# UART_Block.net
KiCad netlist of a schematic drawn in EAGLE
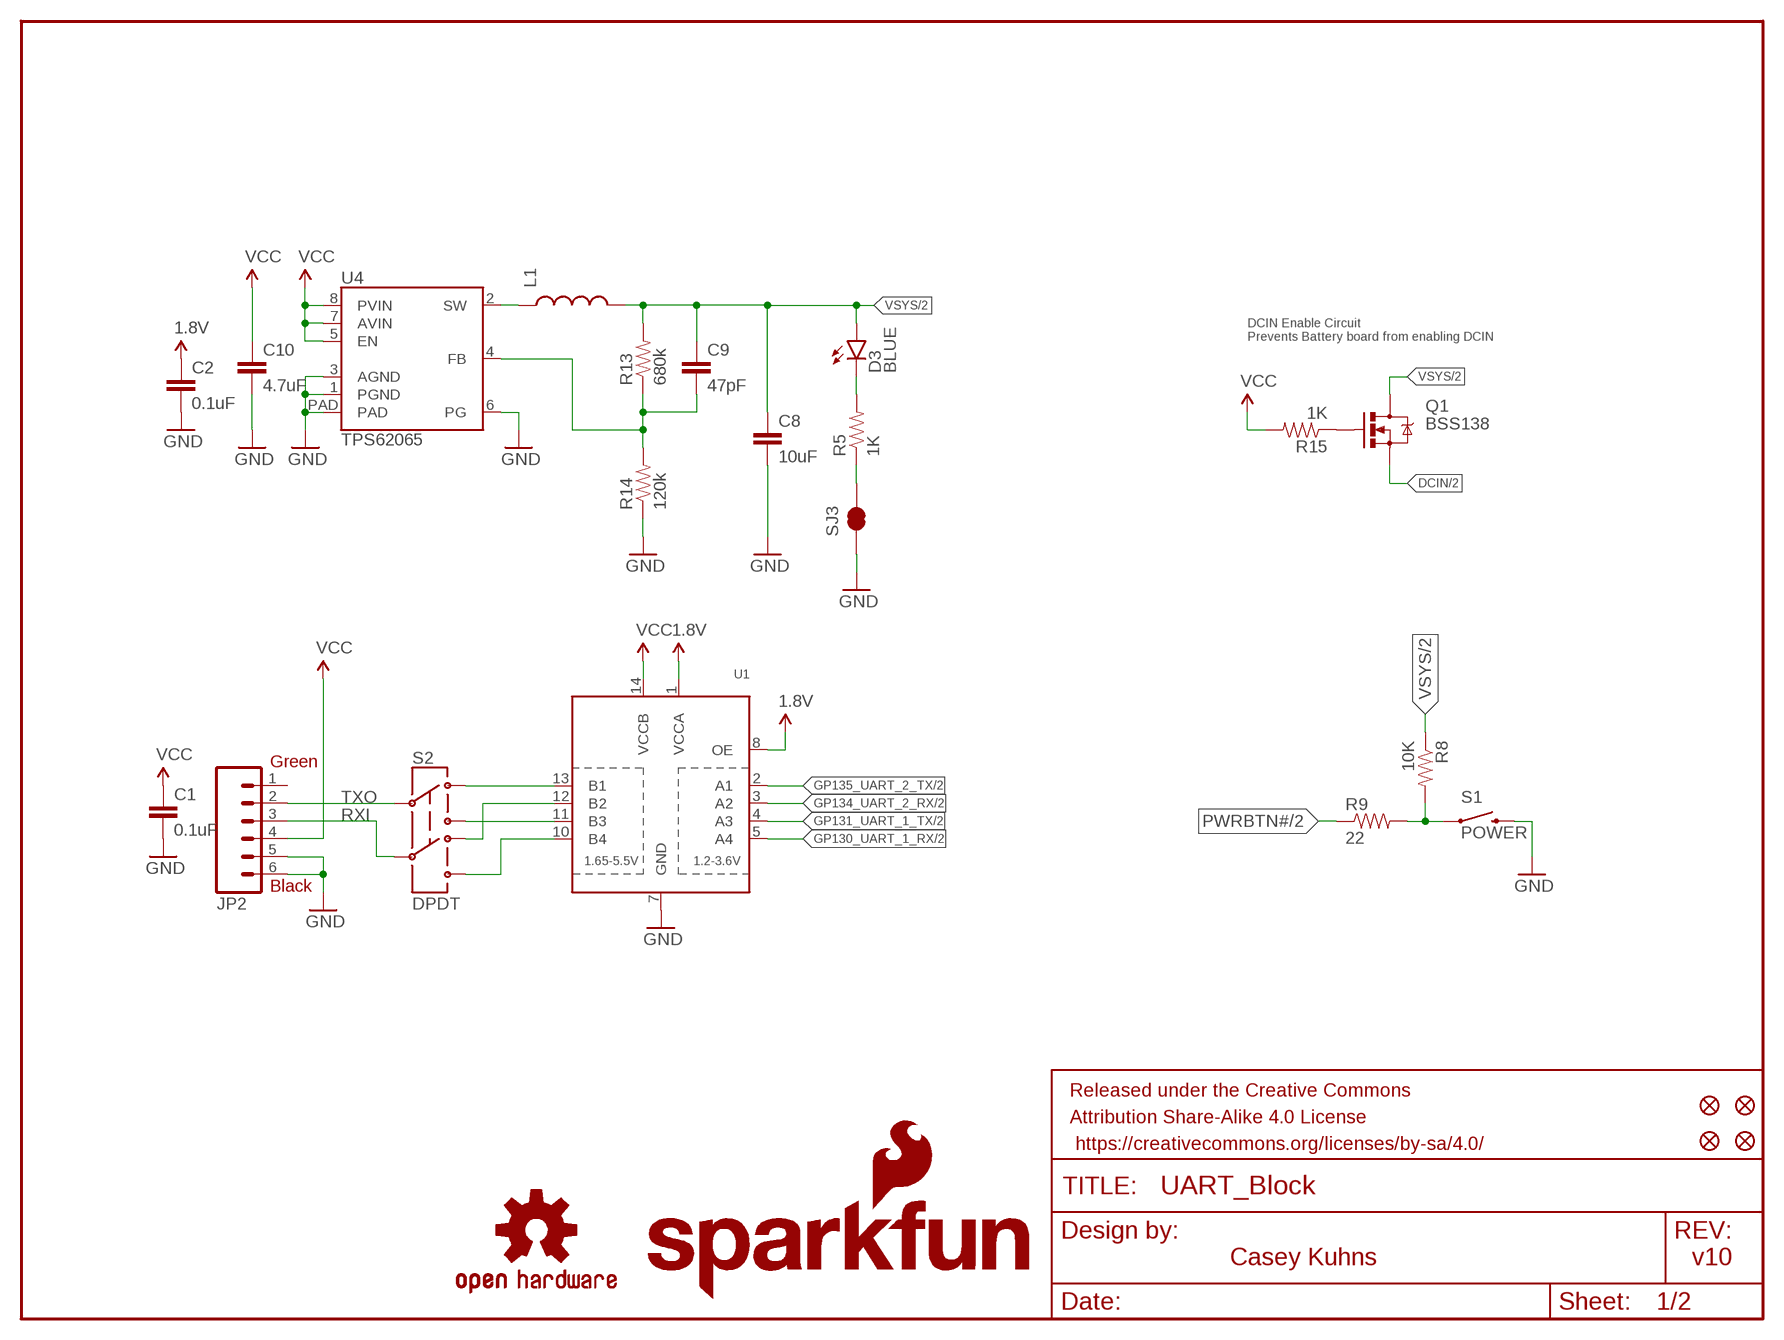
[diagram p0: schematic, sheet 1]
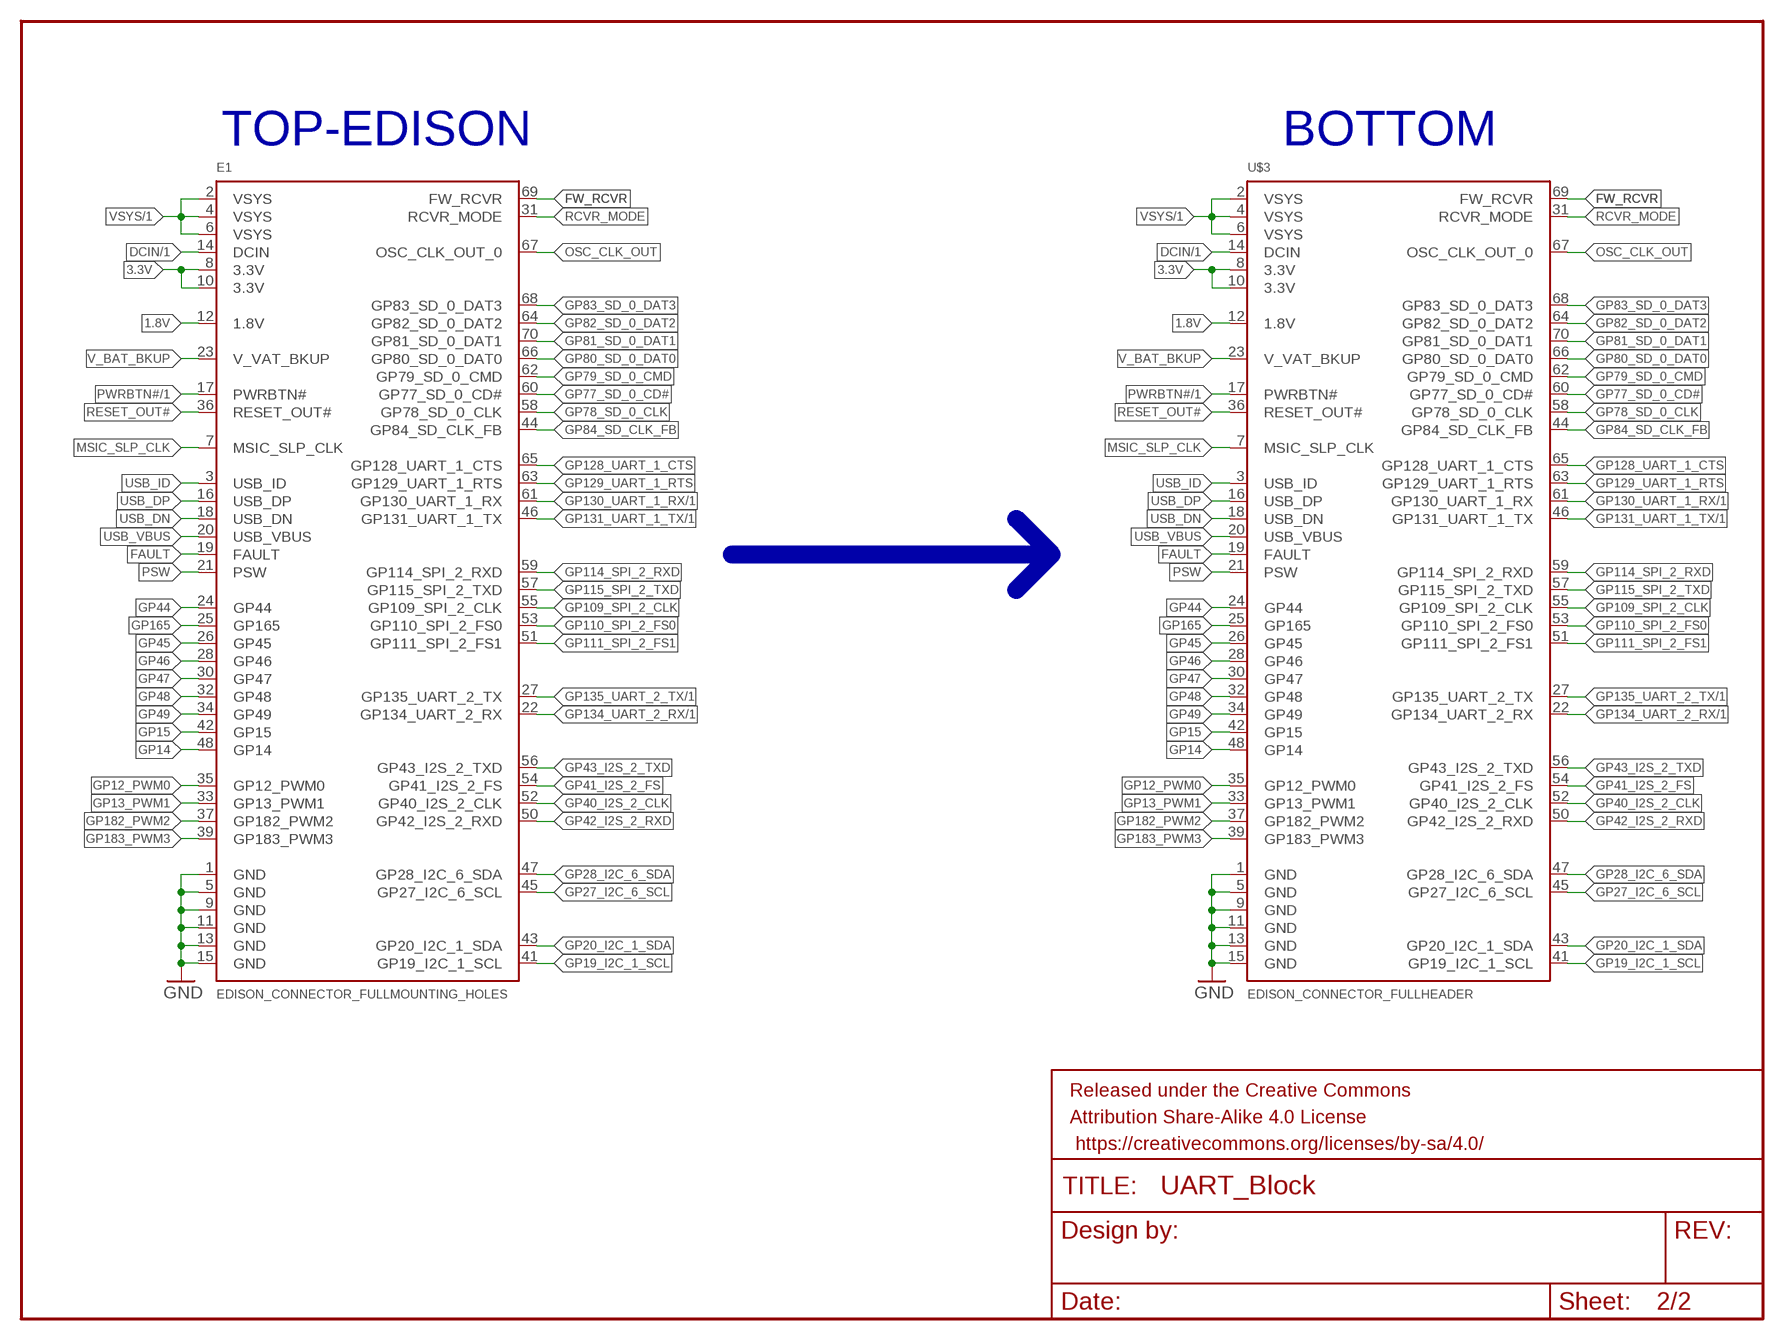
[diagram p1: schematic, sheet 2]

(export (version "E")
  (design (tool "Eeschema 10.0.6"))
  (components
    (comp (ref "E1")
      (value "EDISON_CONNECTOR_FULLMOUNTING_HOLES")
      (footprint "eagle-import:EDISON_DAUGHTER")
      (libsource (lib "eagle-import") (part "EDISON_CONNECTOR_FULLMOUNTING_HOLES"))
    )
    (comp (ref "FRAME2")
      (value "FRAME-LETTER")
      (footprint "eagle-import:CREATIVE_COMMONS")
      (libsource (lib "eagle-import") (part "FRAME-LETTER"))
    )
    (comp (ref "U$3")
      (value "EDISON_CONNECTOR_FULLHEADER")
      (footprint "eagle-import:DF40C-70DP-0.4(51)")
      (libsource (lib "eagle-import") (part "EDISON_CONNECTOR_FULLHEADER"))
    )
    (comp (ref "C1")
      (value "0.1uF")
      (footprint "eagle-import:0603-CAP")
      (libsource (lib "eagle-import") (part "0.1UF-25V(+80/-20%)(0603)"))
    )
    (comp (ref "C2")
      (value "0.1uF")
      (footprint "eagle-import:0603-CAP")
      (libsource (lib "eagle-import") (part "0.1UF-25V(+80/-20%)(0603)"))
    )
    (comp (ref "C8")
      (value "10uF")
      (footprint "eagle-import:1206")
      (libsource (lib "eagle-import") (part "10UF-6.3V-20%(1206)"))
    )
    (comp (ref "C9")
      (value "47pF")
      (footprint "eagle-import:0603-CAP")
      (libsource (lib "eagle-import") (part "47PF-50V-5%(0603)"))
    )
    (comp (ref "C10")
      (value "4.7uF")
      (footprint "eagle-import:0603-CAP")
      (libsource (lib "eagle-import") (part "4.7UF-6.3V-10%(0603)0603"))
    )
    (comp (ref "D3")
      (value "BLUE")
      (footprint "eagle-import:LED-0603")
      (libsource (lib "eagle-import") (part "LED-BLUE0603"))
    )
    (comp (ref "FID1")
      (value "FIDUCIAL1X2")
      (footprint "eagle-import:FIDUCIAL-1X2")
      (libsource (lib "eagle-import") (part "FIDUCIAL1X2"))
    )
    (comp (ref "FID2")
      (value "FIDUCIAL1X2")
      (footprint "eagle-import:FIDUCIAL-1X2")
      (libsource (lib "eagle-import") (part "FIDUCIAL1X2"))
    )
    (comp (ref "FID3")
      (value "FIDUCIAL1X2")
      (footprint "eagle-import:FIDUCIAL-1X2")
      (libsource (lib "eagle-import") (part "FIDUCIAL1X2"))
    )
    (comp (ref "FID4")
      (value "FIDUCIAL1X2")
      (footprint "eagle-import:FIDUCIAL-1X2")
      (libsource (lib "eagle-import") (part "FIDUCIAL1X2"))
    )
    (comp (ref "FRAME1")
      (value "FRAME-LETTER")
      (footprint "eagle-import:CREATIVE_COMMONS")
      (libsource (lib "eagle-import") (part "FRAME-LETTER"))
    )
    (comp (ref "JP2")
      (value "M06SMD")
      (footprint "eagle-import:1X06-SMD")
      (libsource (lib "eagle-import") (part "M06SMD"))
    )
    (comp (ref "L1")
      (value "INDUCTOR")
      (footprint "eagle-import:INDUCTOR-SRP4020")
      (libsource (lib "eagle-import") (part "INDUCTOR"))
    )
    (comp (ref "LOGO1")
      (value "SFE_LOGO_NAME_FLAME.1_INCH")
      (footprint "eagle-import:SFE_LOGO_NAME_FLAME_.1")
      (libsource (lib "eagle-import") (part "SFE_LOGO_NAME_FLAME.1_INCH"))
    )
    (comp (ref "LOGO4")
      (value "OSHW-LOGOS")
      (footprint "eagle-import:OSHW-LOGO-S")
      (libsource (lib "eagle-import") (part "OSHW-LOGOS"))
    )
    (comp (ref "Q1")
      (value "BSS138")
      (footprint "eagle-import:SOT23-3")
      (libsource (lib "eagle-import") (part "MOSFET-NCHANNELBSS138"))
    )
    (comp (ref "R5")
      (value "1K")
      (footprint "eagle-import:0603-RES")
      (libsource (lib "eagle-import") (part "1KOHM1/10W1%(0603)"))
    )
    (comp (ref "R8")
      (value "10K")
      (footprint "eagle-import:0603-RES")
      (libsource (lib "eagle-import") (part "10KOHM1/10W1%(0603)0603"))
    )
    (comp (ref "R9")
      (value "22")
      (footprint "eagle-import:0603-RES")
      (libsource (lib "eagle-import") (part "22OHM1/10W1%(0603)"))
    )
    (comp (ref "R13")
      (value "680k")
      (footprint "eagle-import:0603-RES")
      (libsource (lib "eagle-import") (part "RESISTOR0603"))
    )
    (comp (ref "R14")
      (value "120k")
      (footprint "eagle-import:0603-RES")
      (libsource (lib "eagle-import") (part "RESISTOR0603"))
    )
    (comp (ref "R15")
      (value "1K")
      (footprint "eagle-import:0603-RES")
      (libsource (lib "eagle-import") (part "1KOHM1/10W1%(0603)"))
    )
    (comp (ref "S1")
      (value "POWER")
      (footprint "eagle-import:TACTILE_SWITCH-SMD-RIGHT-ANGLE")
      (libsource (lib "eagle-import") (part "SWITCH-MOMENTARY-2TACTILE-SWITCH-SMD-RIGHT-ANGLE"))
    )
    (comp (ref "S2")
      (value "DPDT")
      (footprint "eagle-import:AYZ0202")
      (libsource (lib "eagle-import") (part "SWITCH-DPDTAYZ0202"))
    )
    (comp (ref "SJ3")
      (value "JUMPER-PAD-2-NC_BY_TRACE")
      (footprint "eagle-import:PAD-JUMPER-2-NC_BY_TRACE_YES_SILK")
      (libsource (lib "eagle-import") (part "JUMPER-PAD-2-NC_BY_TRACE"))
    )
    (comp (ref "U1")
      (value "TXB0104PWRSOIC14")
      (footprint "eagle-import:SO14")
      (libsource (lib "eagle-import") (part "TXB0104PWRSOIC14"))
    )
    (comp (ref "U4")
      (value "TPS62065")
      (footprint "eagle-import:WSON-8-PAD")
      (libsource (lib "eagle-import") (part "TPS62065"))
    )
  )
  (nets
    (net (code "1") (name "1.8V") (class "Default")
      (node (ref "C2") (pin "1") (pinfunction "1_1") (pintype "passive"))
      (node (ref "E1") (pin "12") (pinfunction "1.8V_12") (pintype "bidirectional"))
      (node (ref "U$3") (pin "12") (pinfunction "1.8V_12") (pintype "bidirectional"))
      (node (ref "U1") (pin "1") (pinfunction "VCCA_1") (pintype "bidirectional"))
      (node (ref "U1") (pin "8") (pinfunction "OE_8") (pintype "bidirectional"))
    )
    (net (code "2") (name "3.3V") (class "Default")
      (node (ref "E1") (pin "10") (pinfunction "3.3V_10") (pintype "bidirectional"))
      (node (ref "E1") (pin "8") (pinfunction "3.3V_8") (pintype "bidirectional"))
      (node (ref "U$3") (pin "10") (pinfunction "3.3V_10") (pintype "bidirectional"))
      (node (ref "U$3") (pin "8") (pinfunction "3.3V_8") (pintype "bidirectional"))
    )
    (net (code "3") (name "DCIN") (class "Default")
      (node (ref "E1") (pin "14") (pinfunction "DCIN_14") (pintype "bidirectional"))
      (node (ref "Q1") (pin "2") (pinfunction "S_2") (pintype "passive"))
      (node (ref "U$3") (pin "14") (pinfunction "DCIN_14") (pintype "bidirectional"))
    )
    (net (code "4") (name "FAULT") (class "Default")
      (node (ref "E1") (pin "19") (pinfunction "FAULT_19") (pintype "bidirectional"))
      (node (ref "U$3") (pin "19") (pinfunction "FAULT_19") (pintype "bidirectional"))
    )
    (net (code "5") (name "FW_RCVR") (class "Default")
      (node (ref "E1") (pin "69") (pinfunction "FW_RCVR_69") (pintype "bidirectional"))
      (node (ref "U$3") (pin "69") (pinfunction "FW_RCVR_69") (pintype "bidirectional"))
    )
    (net (code "6") (name "GND") (class "Default")
      (node (ref "C1") (pin "2") (pinfunction "2_2") (pintype "passive"))
      (node (ref "C10") (pin "2") (pinfunction "2_2") (pintype "passive"))
      (node (ref "C2") (pin "2") (pinfunction "2_2") (pintype "passive"))
      (node (ref "C8") (pin "2") (pinfunction "2_2") (pintype "passive"))
      (node (ref "E1") (pin "1") (pinfunction "GND_1") (pintype "bidirectional"))
      (node (ref "E1") (pin "11") (pinfunction "GND_11") (pintype "bidirectional"))
      (node (ref "E1") (pin "13") (pinfunction "GND_13") (pintype "bidirectional"))
      (node (ref "E1") (pin "15") (pinfunction "GND_15") (pintype "bidirectional"))
      (node (ref "E1") (pin "5") (pinfunction "GND_5") (pintype "bidirectional"))
      (node (ref "E1") (pin "9") (pinfunction "GND_9") (pintype "bidirectional"))
      (node (ref "JP2") (pin "5") (pinfunction "5_5") (pintype "passive"))
      (node (ref "JP2") (pin "6") (pinfunction "6_6") (pintype "passive"))
      (node (ref "R14") (pin "1") (pinfunction "1_1") (pintype "passive"))
      (node (ref "S1") (pin "2") (pinfunction "2_2") (pintype "passive"))
      (node (ref "SJ3") (pin "1") (pinfunction "1_1") (pintype "passive"))
      (node (ref "U$3") (pin "1") (pinfunction "GND_1") (pintype "bidirectional"))
      (node (ref "U$3") (pin "11") (pinfunction "GND_11") (pintype "bidirectional"))
      (node (ref "U$3") (pin "13") (pinfunction "GND_13") (pintype "bidirectional"))
      (node (ref "U$3") (pin "15") (pinfunction "GND_15") (pintype "bidirectional"))
      (node (ref "U$3") (pin "5") (pinfunction "GND_5") (pintype "bidirectional"))
      (node (ref "U$3") (pin "9") (pinfunction "GND_9") (pintype "bidirectional"))
      (node (ref "U1") (pin "7") (pinfunction "GND_7") (pintype "bidirectional"))
      (node (ref "U4") (pin "1") (pinfunction "PGND_1") (pintype "bidirectional"))
      (node (ref "U4") (pin "3") (pinfunction "AGND_3") (pintype "bidirectional"))
      (node (ref "U4") (pin "6") (pinfunction "PG_6") (pintype "bidirectional"))
      (node (ref "U4") (pin "PAD") (pinfunction "PAD_PAD") (pintype "bidirectional"))
    )
    (net (code "7") (name "GP12_PWM0") (class "Default")
      (node (ref "E1") (pin "35") (pinfunction "GP12_PWM0_35") (pintype "bidirectional"))
      (node (ref "U$3") (pin "35") (pinfunction "GP12_PWM0_35") (pintype "bidirectional"))
    )
    (net (code "8") (name "GP13_PWM1") (class "Default")
      (node (ref "E1") (pin "33") (pinfunction "GP13_PWM1_33") (pintype "bidirectional"))
      (node (ref "U$3") (pin "33") (pinfunction "GP13_PWM1_33") (pintype "bidirectional"))
    )
    (net (code "9") (name "GP14") (class "Default")
      (node (ref "E1") (pin "48") (pinfunction "GP14_48") (pintype "bidirectional"))
      (node (ref "U$3") (pin "48") (pinfunction "GP14_48") (pintype "bidirectional"))
    )
    (net (code "10") (name "GP15") (class "Default")
      (node (ref "E1") (pin "42") (pinfunction "GP15_42") (pintype "bidirectional"))
      (node (ref "U$3") (pin "42") (pinfunction "GP15_42") (pintype "bidirectional"))
    )
    (net (code "11") (name "GP19_I2C_1_SCL") (class "Default")
      (node (ref "E1") (pin "41") (pinfunction "GP19_I2C_1_SCL_41") (pintype "bidirectional"))
      (node (ref "U$3") (pin "41") (pinfunction "GP19_I2C_1_SCL_41") (pintype "bidirectional"))
    )
    (net (code "12") (name "GP20_I2C_1_SDA") (class "Default")
      (node (ref "E1") (pin "43") (pinfunction "GP20_I2C_1_SDA_43") (pintype "bidirectional"))
      (node (ref "U$3") (pin "43") (pinfunction "GP20_I2C_1_SDA_43") (pintype "bidirectional"))
    )
    (net (code "13") (name "GP27_I2C_6_SCL") (class "Default")
      (node (ref "E1") (pin "45") (pinfunction "GP27_I2C_6_SCL_45") (pintype "bidirectional"))
      (node (ref "U$3") (pin "45") (pinfunction "GP27_I2C_6_SCL_45") (pintype "bidirectional"))
    )
    (net (code "14") (name "GP28_I2C_6_SDA") (class "Default")
      (node (ref "E1") (pin "47") (pinfunction "GP28_I2C_6_SDA_47") (pintype "bidirectional"))
      (node (ref "U$3") (pin "47") (pinfunction "GP28_I2C_6_SDA_47") (pintype "bidirectional"))
    )
    (net (code "15") (name "GP40_I2S_2_CLK") (class "Default")
      (node (ref "E1") (pin "52") (pinfunction "GP40_I2S_2_CLK_52") (pintype "bidirectional"))
      (node (ref "U$3") (pin "52") (pinfunction "GP40_I2S_2_CLK_52") (pintype "bidirectional"))
    )
    (net (code "16") (name "GP41_I2S_2_FS") (class "Default")
      (node (ref "E1") (pin "54") (pinfunction "GP41_I2S_2_FS_54") (pintype "bidirectional"))
      (node (ref "U$3") (pin "54") (pinfunction "GP41_I2S_2_FS_54") (pintype "bidirectional"))
    )
    (net (code "17") (name "GP42_I2S_2_RXD") (class "Default")
      (node (ref "E1") (pin "50") (pinfunction "GP42_I2S_2_RXD_50") (pintype "bidirectional"))
      (node (ref "U$3") (pin "50") (pinfunction "GP42_I2S_2_RXD_50") (pintype "bidirectional"))
    )
    (net (code "18") (name "GP43_I2S_2_TXD") (class "Default")
      (node (ref "E1") (pin "56") (pinfunction "GP43_I2S_2_TXD_56") (pintype "bidirectional"))
      (node (ref "U$3") (pin "56") (pinfunction "GP43_I2S_2_TXD_56") (pintype "bidirectional"))
    )
    (net (code "19") (name "GP44") (class "Default")
      (node (ref "E1") (pin "24") (pinfunction "GP44_24") (pintype "bidirectional"))
      (node (ref "U$3") (pin "24") (pinfunction "GP44_24") (pintype "bidirectional"))
    )
    (net (code "20") (name "GP45") (class "Default")
      (node (ref "E1") (pin "26") (pinfunction "GP45_26") (pintype "bidirectional"))
      (node (ref "U$3") (pin "26") (pinfunction "GP45_26") (pintype "bidirectional"))
    )
    (net (code "21") (name "GP46") (class "Default")
      (node (ref "E1") (pin "28") (pinfunction "GP46_28") (pintype "bidirectional"))
      (node (ref "U$3") (pin "28") (pinfunction "GP46_28") (pintype "bidirectional"))
    )
    (net (code "22") (name "GP47") (class "Default")
      (node (ref "E1") (pin "30") (pinfunction "GP47_30") (pintype "bidirectional"))
      (node (ref "U$3") (pin "30") (pinfunction "GP47_30") (pintype "bidirectional"))
    )
    (net (code "23") (name "GP48") (class "Default")
      (node (ref "E1") (pin "32") (pinfunction "GP48_32") (pintype "bidirectional"))
      (node (ref "U$3") (pin "32") (pinfunction "GP48_32") (pintype "bidirectional"))
    )
    (net (code "24") (name "GP49") (class "Default")
      (node (ref "E1") (pin "34") (pinfunction "GP49_34") (pintype "bidirectional"))
      (node (ref "U$3") (pin "34") (pinfunction "GP49_34") (pintype "bidirectional"))
    )
    (net (code "25") (name "GP77_SD_0_CD#") (class "Default")
      (node (ref "E1") (pin "60") (pinfunction "GP77_SD_0_CD#_60") (pintype "bidirectional"))
      (node (ref "U$3") (pin "60") (pinfunction "GP77_SD_0_CD#_60") (pintype "bidirectional"))
    )
    (net (code "26") (name "GP78_SD_0_CLK") (class "Default")
      (node (ref "E1") (pin "58") (pinfunction "GP78_SD_0_CLK_58") (pintype "bidirectional"))
      (node (ref "U$3") (pin "58") (pinfunction "GP78_SD_0_CLK_58") (pintype "bidirectional"))
    )
    (net (code "27") (name "GP79_SD_0_CMD") (class "Default")
      (node (ref "E1") (pin "62") (pinfunction "GP79_SD_0_CMD_62") (pintype "bidirectional"))
      (node (ref "U$3") (pin "62") (pinfunction "GP79_SD_0_CMD_62") (pintype "bidirectional"))
    )
    (net (code "28") (name "GP80_SD_0_DAT0") (class "Default")
      (node (ref "E1") (pin "66") (pinfunction "GP80_SD_0_DAT0_66") (pintype "bidirectional"))
      (node (ref "U$3") (pin "66") (pinfunction "GP80_SD_0_DAT0_66") (pintype "bidirectional"))
    )
    (net (code "29") (name "GP81_SD_0_DAT1") (class "Default")
      (node (ref "E1") (pin "70") (pinfunction "GP81_SD_0_DAT1_70") (pintype "bidirectional"))
      (node (ref "U$3") (pin "70") (pinfunction "GP81_SD_0_DAT1_70") (pintype "bidirectional"))
    )
    (net (code "30") (name "GP82_SD_0_DAT2") (class "Default")
      (node (ref "E1") (pin "64") (pinfunction "GP82_SD_0_DAT2_64") (pintype "bidirectional"))
      (node (ref "U$3") (pin "64") (pinfunction "GP82_SD_0_DAT2_64") (pintype "bidirectional"))
    )
    (net (code "31") (name "GP83_SD_0_DAT3") (class "Default")
      (node (ref "E1") (pin "68") (pinfunction "GP83_SD_0_DAT3_68") (pintype "bidirectional"))
      (node (ref "U$3") (pin "68") (pinfunction "GP83_SD_0_DAT3_68") (pintype "bidirectional"))
    )
    (net (code "32") (name "GP84_SD_CLK_FB") (class "Default")
      (node (ref "E1") (pin "44") (pinfunction "GP84_SD_CLK_FB_44") (pintype "bidirectional"))
      (node (ref "U$3") (pin "44") (pinfunction "GP84_SD_CLK_FB_44") (pintype "bidirectional"))
    )
    (net (code "33") (name "GP109_SPI_2_CLK") (class "Default")
      (node (ref "E1") (pin "55") (pinfunction "GP109_SPI_2_CLK_55") (pintype "bidirectional"))
      (node (ref "U$3") (pin "55") (pinfunction "GP109_SPI_2_CLK_55") (pintype "bidirectional"))
    )
    (net (code "34") (name "GP110_SPI_2_FS0") (class "Default")
      (node (ref "E1") (pin "53") (pinfunction "GP110_SPI_2_FS0_53") (pintype "bidirectional"))
      (node (ref "U$3") (pin "53") (pinfunction "GP110_SPI_2_FS0_53") (pintype "bidirectional"))
    )
    (net (code "35") (name "GP111_SPI_2_FS1") (class "Default")
      (node (ref "E1") (pin "51") (pinfunction "GP111_SPI_2_FS1_51") (pintype "bidirectional"))
      (node (ref "U$3") (pin "51") (pinfunction "GP111_SPI_2_FS1_51") (pintype "bidirectional"))
    )
    (net (code "36") (name "GP114_SPI_2_RXD") (class "Default")
      (node (ref "E1") (pin "59") (pinfunction "GP114_SPI_2_RXD_59") (pintype "bidirectional"))
      (node (ref "U$3") (pin "59") (pinfunction "GP114_SPI_2_RXD_59") (pintype "bidirectional"))
    )
    (net (code "37") (name "GP115_SPI_2_TXD") (class "Default")
      (node (ref "E1") (pin "57") (pinfunction "GP115_SPI_2_TXD_57") (pintype "bidirectional"))
      (node (ref "U$3") (pin "57") (pinfunction "GP115_SPI_2_TXD_57") (pintype "bidirectional"))
    )
    (net (code "38") (name "GP128_UART_1_CTS") (class "Default")
      (node (ref "E1") (pin "65") (pinfunction "GP128_UART_1_CTS_65") (pintype "bidirectional"))
      (node (ref "U$3") (pin "65") (pinfunction "GP128_UART_1_CTS_65") (pintype "bidirectional"))
    )
    (net (code "39") (name "GP129_UART_1_RTS") (class "Default")
      (node (ref "E1") (pin "63") (pinfunction "GP129_UART_1_RTS_63") (pintype "bidirectional"))
      (node (ref "U$3") (pin "63") (pinfunction "GP129_UART_1_RTS_63") (pintype "bidirectional"))
    )
    (net (code "40") (name "GP130_UART_1_RX") (class "Default")
      (node (ref "E1") (pin "61") (pinfunction "GP130_UART_1_RX_61") (pintype "bidirectional"))
      (node (ref "U$3") (pin "61") (pinfunction "GP130_UART_1_RX_61") (pintype "bidirectional"))
      (node (ref "U1") (pin "5") (pinfunction "A4_5") (pintype "bidirectional"))
    )
    (net (code "41") (name "GP131_UART_1_TX") (class "Default")
      (node (ref "E1") (pin "46") (pinfunction "GP131_UART_1_TX_46") (pintype "bidirectional"))
      (node (ref "U$3") (pin "46") (pinfunction "GP131_UART_1_TX_46") (pintype "bidirectional"))
      (node (ref "U1") (pin "4") (pinfunction "A3_4") (pintype "bidirectional"))
    )
    (net (code "42") (name "GP134_UART_2_RX") (class "Default")
      (node (ref "E1") (pin "22") (pinfunction "GP134_UART_2_RX_22") (pintype "bidirectional"))
      (node (ref "U$3") (pin "22") (pinfunction "GP134_UART_2_RX_22") (pintype "bidirectional"))
      (node (ref "U1") (pin "3") (pinfunction "A2_3") (pintype "bidirectional"))
    )
    (net (code "43") (name "GP135_UART_2_TX") (class "Default")
      (node (ref "E1") (pin "27") (pinfunction "GP135_UART_2_TX_27") (pintype "bidirectional"))
      (node (ref "U$3") (pin "27") (pinfunction "GP135_UART_2_TX_27") (pintype "bidirectional"))
      (node (ref "U1") (pin "2") (pinfunction "A1_2") (pintype "bidirectional"))
    )
    (net (code "44") (name "GP165") (class "Default")
      (node (ref "E1") (pin "25") (pinfunction "GP165_25") (pintype "bidirectional"))
      (node (ref "U$3") (pin "25") (pinfunction "GP165_25") (pintype "bidirectional"))
    )
    (net (code "45") (name "GP182_PWM2") (class "Default")
      (node (ref "E1") (pin "37") (pinfunction "GP182_PWM2_37") (pintype "bidirectional"))
      (node (ref "U$3") (pin "37") (pinfunction "GP182_PWM2_37") (pintype "bidirectional"))
    )
    (net (code "46") (name "GP183_PWM3") (class "Default")
      (node (ref "E1") (pin "39") (pinfunction "GP183_PWM3_39") (pintype "bidirectional"))
      (node (ref "U$3") (pin "39") (pinfunction "GP183_PWM3_39") (pintype "bidirectional"))
    )
    (net (code "47") (name "MSIC_SLP_CLK") (class "Default")
      (node (ref "E1") (pin "7") (pinfunction "MSIC_SLP_CLK_7") (pintype "bidirectional"))
      (node (ref "U$3") (pin "7") (pinfunction "MSIC_SLP_CLK_7") (pintype "bidirectional"))
    )
    (net (code "48") (name "Net-(D3-PadC)") (class "Default")
      (node (ref "D3") (pin "C") (pinfunction "C_C") (pintype "passive"))
      (node (ref "R5") (pin "2") (pinfunction "2_2") (pintype "passive"))
    )
    (net (code "49") (name "Net-(L1-1)") (class "Default")
      (node (ref "L1") (pin "P$1") (pinfunction "1_P$1") (pintype "passive"))
      (node (ref "U4") (pin "2") (pinfunction "SW_2") (pintype "bidirectional"))
    )
    (net (code "50") (name "Net-(Q1-G)") (class "Default")
      (node (ref "Q1") (pin "1") (pinfunction "G_1") (pintype "passive"))
      (node (ref "R15") (pin "1") (pinfunction "1_1") (pintype "passive"))
    )
    (net (code "51") (name "Net-(R5-Pad1)") (class "Default")
      (node (ref "R5") (pin "1") (pinfunction "1_1") (pintype "passive"))
      (node (ref "SJ3") (pin "2") (pinfunction "2_2") (pintype "passive"))
    )
    (net (code "52") (name "Net-(R8-Pad2)") (class "Default")
      (node (ref "R8") (pin "2") (pinfunction "2_2") (pintype "passive"))
      (node (ref "R9") (pin "2") (pinfunction "2_2") (pintype "passive"))
      (node (ref "S1") (pin "1") (pinfunction "1_1") (pintype "passive"))
    )
    (net (code "53") (name "Net-(U1-B1)") (class "Default")
      (node (ref "S2") (pin "1") (pinfunction "1_1") (pintype "bidirectional"))
      (node (ref "U1") (pin "13") (pinfunction "B1_13") (pintype "bidirectional"))
    )
    (net (code "54") (name "Net-(U1-B2)") (class "Default")
      (node (ref "S2") (pin "4") (pinfunction "4_4") (pintype "bidirectional"))
      (node (ref "U1") (pin "12") (pinfunction "B2_12") (pintype "bidirectional"))
    )
    (net (code "55") (name "Net-(U1-B3)") (class "Default")
      (node (ref "S2") (pin "3") (pinfunction "3_3") (pintype "bidirectional"))
      (node (ref "U1") (pin "11") (pinfunction "B3_11") (pintype "bidirectional"))
    )
    (net (code "56") (name "Net-(U1-B4)") (class "Default")
      (node (ref "S2") (pin "6") (pinfunction "6_6") (pintype "bidirectional"))
      (node (ref "U1") (pin "10") (pinfunction "B4_10") (pintype "bidirectional"))
    )
    (net (code "57") (name "Net-(U4-FB)") (class "Default")
      (node (ref "C9") (pin "2") (pinfunction "2_2") (pintype "passive"))
      (node (ref "R13") (pin "1") (pinfunction "1_1") (pintype "passive"))
      (node (ref "R14") (pin "2") (pinfunction "2_2") (pintype "passive"))
      (node (ref "U4") (pin "4") (pinfunction "FB_4") (pintype "bidirectional"))
    )
    (net (code "58") (name "OSC_CLK_OUT") (class "Default")
      (node (ref "E1") (pin "67") (pinfunction "OSC_CLK_OUT_0_67") (pintype "bidirectional"))
      (node (ref "U$3") (pin "67") (pinfunction "OSC_CLK_OUT_0_67") (pintype "bidirectional"))
    )
    (net (code "59") (name "PSW") (class "Default")
      (node (ref "E1") (pin "21") (pinfunction "PSW_21") (pintype "bidirectional"))
      (node (ref "U$3") (pin "21") (pinfunction "PSW_21") (pintype "bidirectional"))
    )
    (net (code "60") (name "PWRBTN#") (class "Default")
      (node (ref "E1") (pin "17") (pinfunction "PWRBTN#_17") (pintype "bidirectional"))
      (node (ref "R9") (pin "1") (pinfunction "1_1") (pintype "passive"))
      (node (ref "U$3") (pin "17") (pinfunction "PWRBTN#_17") (pintype "bidirectional"))
    )
    (net (code "61") (name "RCVR_MODE") (class "Default")
      (node (ref "E1") (pin "31") (pinfunction "RCVR_MODE_31") (pintype "bidirectional"))
      (node (ref "U$3") (pin "31") (pinfunction "RCVR_MODE_31") (pintype "bidirectional"))
    )
    (net (code "62") (name "RESET_OUT#") (class "Default")
      (node (ref "E1") (pin "36") (pinfunction "RESET_OUT#_36") (pintype "bidirectional"))
      (node (ref "U$3") (pin "36") (pinfunction "RESET_OUT#_36") (pintype "bidirectional"))
    )
    (net (code "63") (name "RXI") (class "Default")
      (node (ref "JP2") (pin "3") (pinfunction "3_3") (pintype "passive"))
      (node (ref "S2") (pin "5") (pinfunction "5_5") (pintype "bidirectional"))
    )
    (net (code "64") (name "TXO") (class "Default")
      (node (ref "JP2") (pin "2") (pinfunction "2_2") (pintype "passive"))
      (node (ref "S2") (pin "2") (pinfunction "2_2") (pintype "bidirectional"))
    )
    (net (code "65") (name "USB_DN") (class "Default")
      (node (ref "E1") (pin "18") (pinfunction "USB_DN_18") (pintype "bidirectional"))
      (node (ref "U$3") (pin "18") (pinfunction "USB_DN_18") (pintype "bidirectional"))
    )
    (net (code "66") (name "USB_DP") (class "Default")
      (node (ref "E1") (pin "16") (pinfunction "USB_DP_16") (pintype "bidirectional"))
      (node (ref "U$3") (pin "16") (pinfunction "USB_DP_16") (pintype "bidirectional"))
    )
    (net (code "67") (name "USB_ID") (class "Default")
      (node (ref "E1") (pin "3") (pinfunction "USB_ID_3") (pintype "bidirectional"))
      (node (ref "U$3") (pin "3") (pinfunction "USB_ID_3") (pintype "bidirectional"))
    )
    (net (code "68") (name "USB_VBUS") (class "Default")
      (node (ref "E1") (pin "20") (pinfunction "USB_VBUS_20") (pintype "bidirectional"))
      (node (ref "U$3") (pin "20") (pinfunction "USB_VBUS_20") (pintype "bidirectional"))
    )
    (net (code "69") (name "VCC") (class "Default")
      (node (ref "C1") (pin "1") (pinfunction "1_1") (pintype "passive"))
      (node (ref "C10") (pin "1") (pinfunction "1_1") (pintype "passive"))
      (node (ref "JP2") (pin "4") (pinfunction "4_4") (pintype "passive"))
      (node (ref "R15") (pin "2") (pinfunction "2_2") (pintype "passive"))
      (node (ref "U1") (pin "14") (pinfunction "VCCB_14") (pintype "bidirectional"))
      (node (ref "U4") (pin "5") (pinfunction "EN_5") (pintype "bidirectional"))
      (node (ref "U4") (pin "7") (pinfunction "AVIN_7") (pintype "bidirectional"))
      (node (ref "U4") (pin "8") (pinfunction "PVIN_8") (pintype "bidirectional"))
    )
    (net (code "70") (name "VSYS") (class "Default")
      (node (ref "C8") (pin "1") (pinfunction "1_1") (pintype "passive"))
      (node (ref "C9") (pin "1") (pinfunction "1_1") (pintype "passive"))
      (node (ref "D3") (pin "A") (pinfunction "A_A") (pintype "passive"))
      (node (ref "E1") (pin "2") (pinfunction "VSYS_2") (pintype "bidirectional"))
      (node (ref "E1") (pin "4") (pinfunction "VSYS_4") (pintype "bidirectional"))
      (node (ref "E1") (pin "6") (pinfunction "VSYS_6") (pintype "bidirectional"))
      (node (ref "L1") (pin "P$2") (pinfunction "2_P$2") (pintype "passive"))
      (node (ref "Q1") (pin "3") (pinfunction "D_3") (pintype "passive"))
      (node (ref "R13") (pin "2") (pinfunction "2_2") (pintype "passive"))
      (node (ref "R8") (pin "1") (pinfunction "1_1") (pintype "passive"))
      (node (ref "U$3") (pin "2") (pinfunction "VSYS_2") (pintype "bidirectional"))
      (node (ref "U$3") (pin "4") (pinfunction "VSYS_4") (pintype "bidirectional"))
      (node (ref "U$3") (pin "6") (pinfunction "VSYS_6") (pintype "bidirectional"))
    )
    (net (code "71") (name "V_BAT_BKUP") (class "Default")
      (node (ref "E1") (pin "23") (pinfunction "V_VAT_BKUP_23") (pintype "bidirectional"))
      (node (ref "U$3") (pin "23") (pinfunction "V_VAT_BKUP_23") (pintype "bidirectional"))
    )
    (net (code "72") (name "unconnected-(JP2-Pad1)") (class "Default")
      (node (ref "JP2") (pin "1") (pinfunction "1_1") (pintype "passive"))
    )
  )
)
